# backplane.net
KiCad netlist of a schematic drawn in EAGLE
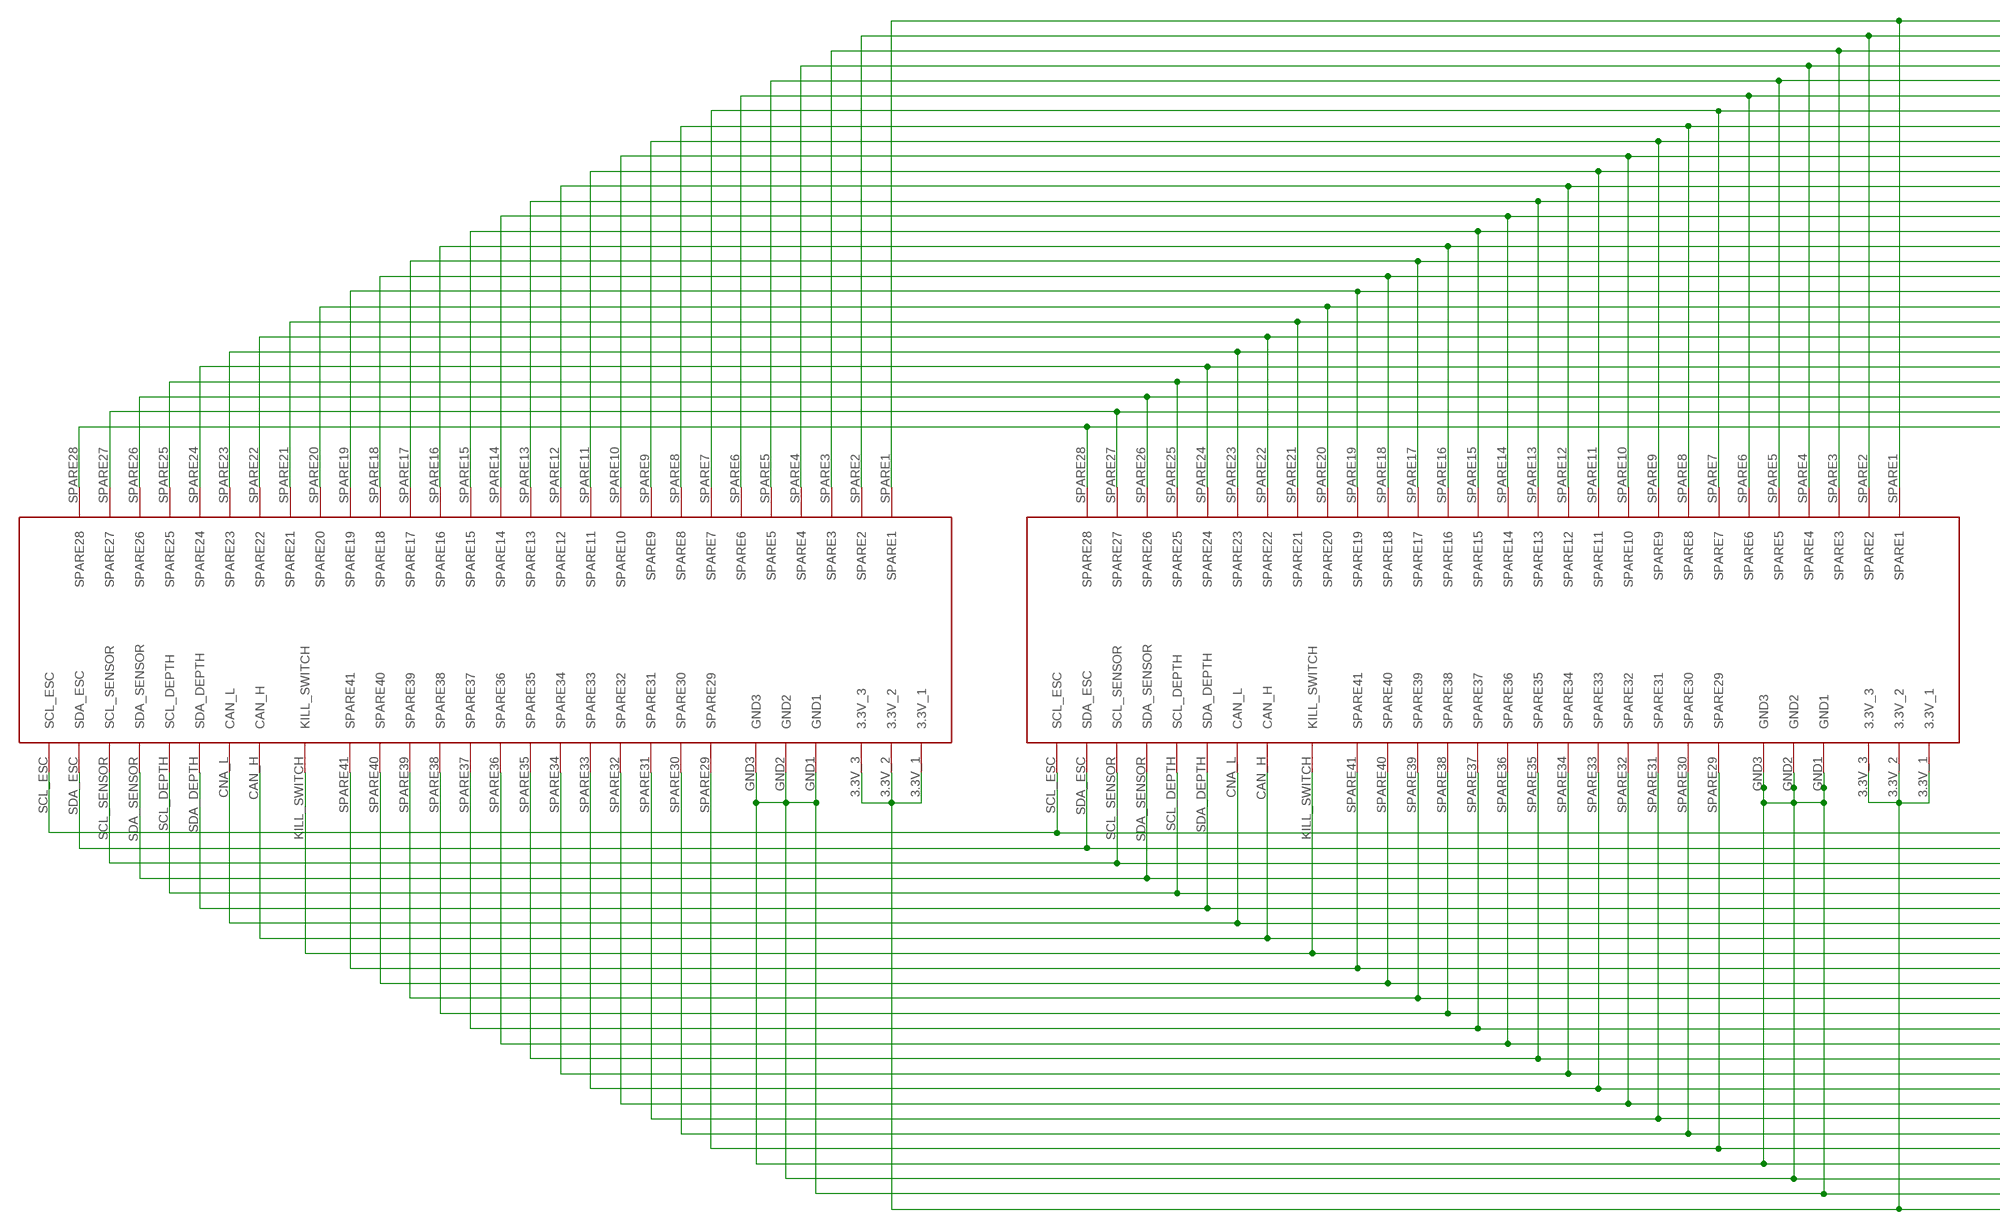
[diagram p0: schematic, sheet 1, part 1 of 2]
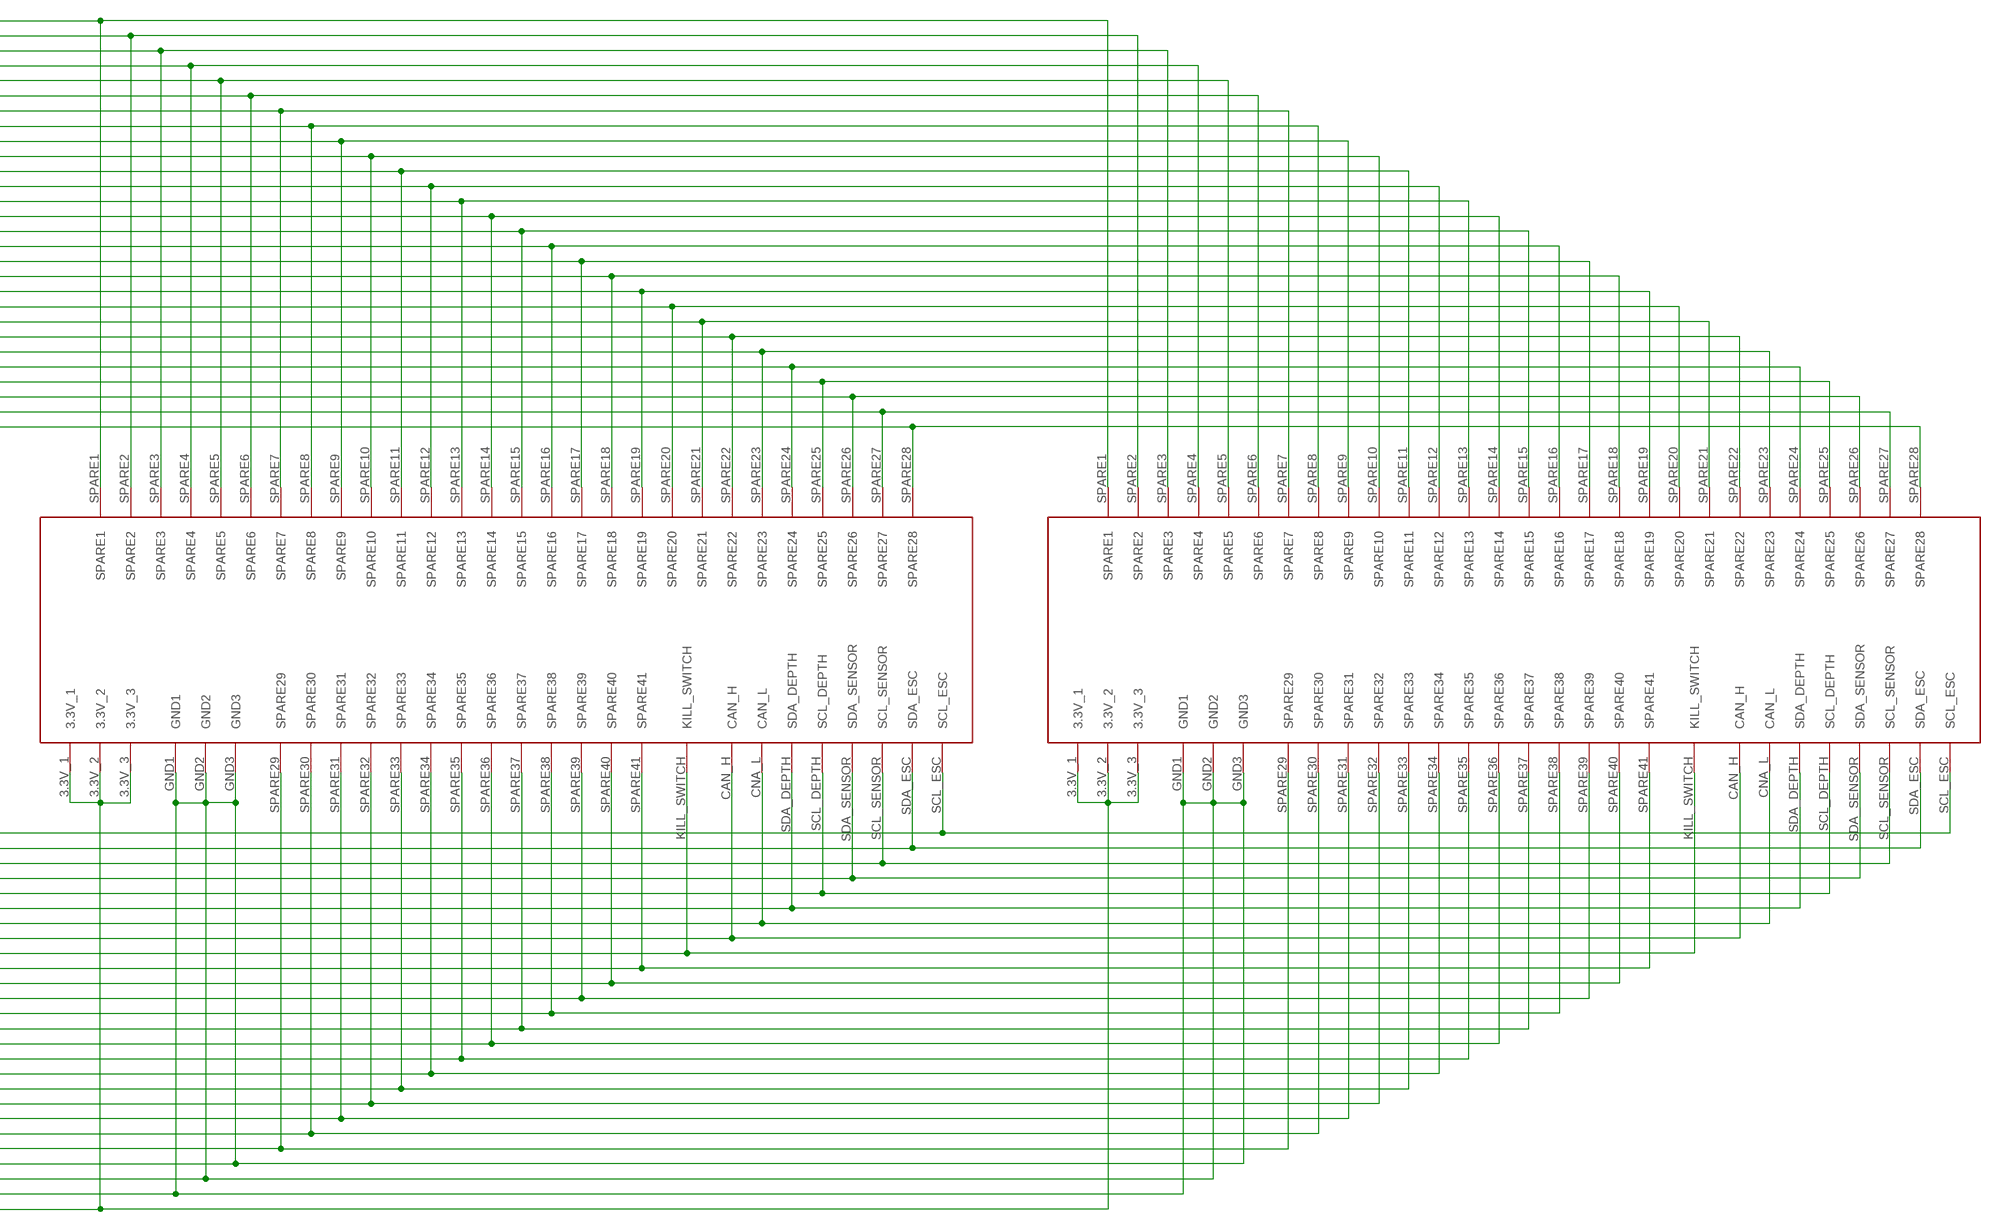
[diagram p1: schematic, sheet 1, part 2 of 2]

(export (version "E")
  (design (tool "Eeschema 10.0.6"))
  (components
    (comp (ref "CO-PROCESSOR")
      (value "5530843_MATE")
      (footprint "eagle-import:5530843-6-BACKPLANEMATE")
      (libsource (lib "eagle-import") (part "5530843_MATE"))
    )
    (comp (ref "CONVERTER")
      (value "5530843_MATE")
      (footprint "eagle-import:5530843-6-BACKPLANEMATE")
      (libsource (lib "eagle-import") (part "5530843_MATE"))
    )
    (comp (ref "EXTRA")
      (value "5530843_MATE")
      (footprint "eagle-import:5530843-6-BACKPLANEMATE")
      (libsource (lib "eagle-import") (part "5530843_MATE"))
    )
    (comp (ref "LOAD_BALANCER")
      (value "5530843_MATE")
      (footprint "eagle-import:5530843-6-BACKPLANEMATE")
      (libsource (lib "eagle-import") (part "5530843_MATE"))
    )
  )
  (nets
    (net (code "1") (name "/3.3") (class "Default")
      (node (ref "CO-PROCESSOR") (pin "3.3V_1") (pinfunction "3.3V_1_3.3V_1") (pintype "bidirectional"))
      (node (ref "CO-PROCESSOR") (pin "3.3V_2") (pinfunction "3.3V_2_3.3V_2") (pintype "bidirectional"))
      (node (ref "CO-PROCESSOR") (pin "3.3V_3") (pinfunction "3.3V_3_3.3V_3") (pintype "bidirectional"))
      (node (ref "CO-PROCESSOR") (pin "SPARE1") (pinfunction "SPARE1_SPARE1") (pintype "bidirectional"))
      (node (ref "CO-PROCESSOR") (pin "SPARE2") (pinfunction "SPARE2_SPARE2") (pintype "bidirectional"))
      (node (ref "CO-PROCESSOR") (pin "SPARE3") (pinfunction "SPARE3_SPARE3") (pintype "bidirectional"))
      (node (ref "CONVERTER") (pin "3.3V_1") (pinfunction "3.3V_1_3.3V_1") (pintype "bidirectional"))
      (node (ref "CONVERTER") (pin "3.3V_2") (pinfunction "3.3V_2_3.3V_2") (pintype "bidirectional"))
      (node (ref "CONVERTER") (pin "3.3V_3") (pinfunction "3.3V_3_3.3V_3") (pintype "bidirectional"))
      (node (ref "CONVERTER") (pin "SPARE1") (pinfunction "SPARE1_SPARE1") (pintype "bidirectional"))
      (node (ref "CONVERTER") (pin "SPARE2") (pinfunction "SPARE2_SPARE2") (pintype "bidirectional"))
      (node (ref "CONVERTER") (pin "SPARE3") (pinfunction "SPARE3_SPARE3") (pintype "bidirectional"))
      (node (ref "EXTRA") (pin "3.3V_1") (pinfunction "3.3V_1_3.3V_1") (pintype "bidirectional"))
      (node (ref "EXTRA") (pin "3.3V_2") (pinfunction "3.3V_2_3.3V_2") (pintype "bidirectional"))
      (node (ref "EXTRA") (pin "3.3V_3") (pinfunction "3.3V_3_3.3V_3") (pintype "bidirectional"))
      (node (ref "EXTRA") (pin "SPARE1") (pinfunction "SPARE1_SPARE1") (pintype "bidirectional"))
      (node (ref "EXTRA") (pin "SPARE2") (pinfunction "SPARE2_SPARE2") (pintype "bidirectional"))
      (node (ref "EXTRA") (pin "SPARE3") (pinfunction "SPARE3_SPARE3") (pintype "bidirectional"))
      (node (ref "LOAD_BALANCER") (pin "3.3V_1") (pinfunction "3.3V_1_3.3V_1") (pintype "bidirectional"))
      (node (ref "LOAD_BALANCER") (pin "3.3V_2") (pinfunction "3.3V_2_3.3V_2") (pintype "bidirectional"))
      (node (ref "LOAD_BALANCER") (pin "3.3V_3") (pinfunction "3.3V_3_3.3V_3") (pintype "bidirectional"))
      (node (ref "LOAD_BALANCER") (pin "SPARE1") (pinfunction "SPARE1_SPARE1") (pintype "bidirectional"))
      (node (ref "LOAD_BALANCER") (pin "SPARE2") (pinfunction "SPARE2_SPARE2") (pintype "bidirectional"))
      (node (ref "LOAD_BALANCER") (pin "SPARE3") (pinfunction "SPARE3_SPARE3") (pintype "bidirectional"))
    )
    (net (code "2") (name "/GND") (class "Default")
      (node (ref "CO-PROCESSOR") (pin "GND1") (pinfunction "GND1_GND1") (pintype "bidirectional"))
      (node (ref "CO-PROCESSOR") (pin "GND2") (pinfunction "GND2_GND2") (pintype "bidirectional"))
      (node (ref "CO-PROCESSOR") (pin "GND3") (pinfunction "GND3_GND3") (pintype "bidirectional"))
      (node (ref "CO-PROCESSOR") (pin "SPARE4") (pinfunction "SPARE4_SPARE4") (pintype "bidirectional"))
      (node (ref "CO-PROCESSOR") (pin "SPARE5") (pinfunction "SPARE5_SPARE5") (pintype "bidirectional"))
      (node (ref "CO-PROCESSOR") (pin "SPARE6") (pinfunction "SPARE6_SPARE6") (pintype "bidirectional"))
      (node (ref "CONVERTER") (pin "GND1") (pinfunction "GND1_GND1") (pintype "bidirectional"))
      (node (ref "CONVERTER") (pin "GND2") (pinfunction "GND2_GND2") (pintype "bidirectional"))
      (node (ref "CONVERTER") (pin "GND3") (pinfunction "GND3_GND3") (pintype "bidirectional"))
      (node (ref "CONVERTER") (pin "SPARE4") (pinfunction "SPARE4_SPARE4") (pintype "bidirectional"))
      (node (ref "CONVERTER") (pin "SPARE5") (pinfunction "SPARE5_SPARE5") (pintype "bidirectional"))
      (node (ref "CONVERTER") (pin "SPARE6") (pinfunction "SPARE6_SPARE6") (pintype "bidirectional"))
      (node (ref "EXTRA") (pin "GND1") (pinfunction "GND1_GND1") (pintype "bidirectional"))
      (node (ref "EXTRA") (pin "GND2") (pinfunction "GND2_GND2") (pintype "bidirectional"))
      (node (ref "EXTRA") (pin "GND3") (pinfunction "GND3_GND3") (pintype "bidirectional"))
      (node (ref "EXTRA") (pin "SPARE4") (pinfunction "SPARE4_SPARE4") (pintype "bidirectional"))
      (node (ref "EXTRA") (pin "SPARE5") (pinfunction "SPARE5_SPARE5") (pintype "bidirectional"))
      (node (ref "EXTRA") (pin "SPARE6") (pinfunction "SPARE6_SPARE6") (pintype "bidirectional"))
      (node (ref "LOAD_BALANCER") (pin "GND1") (pinfunction "GND1_GND1") (pintype "bidirectional"))
      (node (ref "LOAD_BALANCER") (pin "GND2") (pinfunction "GND2_GND2") (pintype "bidirectional"))
      (node (ref "LOAD_BALANCER") (pin "GND3") (pinfunction "GND3_GND3") (pintype "bidirectional"))
      (node (ref "LOAD_BALANCER") (pin "SPARE4") (pinfunction "SPARE4_SPARE4") (pintype "bidirectional"))
      (node (ref "LOAD_BALANCER") (pin "SPARE5") (pinfunction "SPARE5_SPARE5") (pintype "bidirectional"))
      (node (ref "LOAD_BALANCER") (pin "SPARE6") (pinfunction "SPARE6_SPARE6") (pintype "bidirectional"))
    )
    (net (code "3") (name "Net-(CO-PROCESSOR-CAN_L)") (class "Default")
      (node (ref "CO-PROCESSOR") (pin "CNA_L") (pinfunction "CAN_L_CNA_L") (pintype "bidirectional"))
      (node (ref "CONVERTER") (pin "CNA_L") (pinfunction "CAN_L_CNA_L") (pintype "bidirectional"))
      (node (ref "EXTRA") (pin "CNA_L") (pinfunction "CAN_L_CNA_L") (pintype "bidirectional"))
      (node (ref "LOAD_BALANCER") (pin "CNA_L") (pinfunction "CAN_L_CNA_L") (pintype "bidirectional"))
    )
    (net (code "4") (name "Net-(CO-PROCESSOR-PadCAN_H)") (class "Default")
      (node (ref "CO-PROCESSOR") (pin "CAN_H") (pinfunction "CAN_H_CAN_H") (pintype "bidirectional"))
      (node (ref "CONVERTER") (pin "CAN_H") (pinfunction "CAN_H_CAN_H") (pintype "bidirectional"))
      (node (ref "EXTRA") (pin "CAN_H") (pinfunction "CAN_H_CAN_H") (pintype "bidirectional"))
      (node (ref "LOAD_BALANCER") (pin "CAN_H") (pinfunction "CAN_H_CAN_H") (pintype "bidirectional"))
    )
    (net (code "5") (name "Net-(CO-PROCESSOR-PadKILL_SWITCH)") (class "Default")
      (node (ref "CO-PROCESSOR") (pin "KILL_SWITCH") (pinfunction "KILL_SWITCH_KILL_SWITCH") (pintype "bidirectional"))
      (node (ref "CONVERTER") (pin "KILL_SWITCH") (pinfunction "KILL_SWITCH_KILL_SWITCH") (pintype "bidirectional"))
      (node (ref "EXTRA") (pin "KILL_SWITCH") (pinfunction "KILL_SWITCH_KILL_SWITCH") (pintype "bidirectional"))
      (node (ref "LOAD_BALANCER") (pin "KILL_SWITCH") (pinfunction "KILL_SWITCH_KILL_SWITCH") (pintype "bidirectional"))
    )
    (net (code "6") (name "Net-(CO-PROCESSOR-PadSCL_DEPTH)") (class "Default")
      (node (ref "CO-PROCESSOR") (pin "SCL_DEPTH") (pinfunction "SCL_DEPTH_SCL_DEPTH") (pintype "bidirectional"))
      (node (ref "CONVERTER") (pin "SCL_DEPTH") (pinfunction "SCL_DEPTH_SCL_DEPTH") (pintype "bidirectional"))
      (node (ref "EXTRA") (pin "SCL_DEPTH") (pinfunction "SCL_DEPTH_SCL_DEPTH") (pintype "bidirectional"))
      (node (ref "LOAD_BALANCER") (pin "SCL_DEPTH") (pinfunction "SCL_DEPTH_SCL_DEPTH") (pintype "bidirectional"))
    )
    (net (code "7") (name "Net-(CO-PROCESSOR-PadSCL_ESC)") (class "Default")
      (node (ref "CO-PROCESSOR") (pin "SCL_ESC") (pinfunction "SCL_ESC_SCL_ESC") (pintype "bidirectional"))
      (node (ref "CONVERTER") (pin "SCL_ESC") (pinfunction "SCL_ESC_SCL_ESC") (pintype "bidirectional"))
      (node (ref "EXTRA") (pin "SCL_ESC") (pinfunction "SCL_ESC_SCL_ESC") (pintype "bidirectional"))
      (node (ref "LOAD_BALANCER") (pin "SCL_ESC") (pinfunction "SCL_ESC_SCL_ESC") (pintype "bidirectional"))
    )
    (net (code "8") (name "Net-(CO-PROCESSOR-PadSCL_SENSOR)") (class "Default")
      (node (ref "CO-PROCESSOR") (pin "SCL_SENSOR") (pinfunction "SCL_SENSOR_SCL_SENSOR") (pintype "bidirectional"))
      (node (ref "CONVERTER") (pin "SCL_SENSOR") (pinfunction "SCL_SENSOR_SCL_SENSOR") (pintype "bidirectional"))
      (node (ref "EXTRA") (pin "SCL_SENSOR") (pinfunction "SCL_SENSOR_SCL_SENSOR") (pintype "bidirectional"))
      (node (ref "LOAD_BALANCER") (pin "SCL_SENSOR") (pinfunction "SCL_SENSOR_SCL_SENSOR") (pintype "bidirectional"))
    )
    (net (code "9") (name "Net-(CO-PROCESSOR-PadSDA_DEPTH)") (class "Default")
      (node (ref "CO-PROCESSOR") (pin "SDA_DEPTH") (pinfunction "SDA_DEPTH_SDA_DEPTH") (pintype "bidirectional"))
      (node (ref "CONVERTER") (pin "SDA_DEPTH") (pinfunction "SDA_DEPTH_SDA_DEPTH") (pintype "bidirectional"))
      (node (ref "EXTRA") (pin "SDA_DEPTH") (pinfunction "SDA_DEPTH_SDA_DEPTH") (pintype "bidirectional"))
      (node (ref "LOAD_BALANCER") (pin "SDA_DEPTH") (pinfunction "SDA_DEPTH_SDA_DEPTH") (pintype "bidirectional"))
    )
    (net (code "10") (name "Net-(CO-PROCESSOR-PadSDA_ESC)") (class "Default")
      (node (ref "CO-PROCESSOR") (pin "SDA_ESC") (pinfunction "SDA_ESC_SDA_ESC") (pintype "bidirectional"))
      (node (ref "CONVERTER") (pin "SDA_ESC") (pinfunction "SDA_ESC_SDA_ESC") (pintype "bidirectional"))
      (node (ref "EXTRA") (pin "SDA_ESC") (pinfunction "SDA_ESC_SDA_ESC") (pintype "bidirectional"))
      (node (ref "LOAD_BALANCER") (pin "SDA_ESC") (pinfunction "SDA_ESC_SDA_ESC") (pintype "bidirectional"))
    )
    (net (code "11") (name "Net-(CO-PROCESSOR-PadSDA_SENSOR)") (class "Default")
      (node (ref "CO-PROCESSOR") (pin "SDA_SENSOR") (pinfunction "SDA_SENSOR_SDA_SENSOR") (pintype "bidirectional"))
      (node (ref "CONVERTER") (pin "SDA_SENSOR") (pinfunction "SDA_SENSOR_SDA_SENSOR") (pintype "bidirectional"))
      (node (ref "EXTRA") (pin "SDA_SENSOR") (pinfunction "SDA_SENSOR_SDA_SENSOR") (pintype "bidirectional"))
      (node (ref "LOAD_BALANCER") (pin "SDA_SENSOR") (pinfunction "SDA_SENSOR_SDA_SENSOR") (pintype "bidirectional"))
    )
    (net (code "12") (name "Net-(CO-PROCESSOR-PadSPARE7)") (class "Default")
      (node (ref "CO-PROCESSOR") (pin "SPARE7") (pinfunction "SPARE7_SPARE7") (pintype "bidirectional"))
      (node (ref "CONVERTER") (pin "SPARE7") (pinfunction "SPARE7_SPARE7") (pintype "bidirectional"))
      (node (ref "EXTRA") (pin "SPARE7") (pinfunction "SPARE7_SPARE7") (pintype "bidirectional"))
      (node (ref "LOAD_BALANCER") (pin "SPARE7") (pinfunction "SPARE7_SPARE7") (pintype "bidirectional"))
    )
    (net (code "13") (name "Net-(CO-PROCESSOR-PadSPARE8)") (class "Default")
      (node (ref "CO-PROCESSOR") (pin "SPARE8") (pinfunction "SPARE8_SPARE8") (pintype "bidirectional"))
      (node (ref "CONVERTER") (pin "SPARE8") (pinfunction "SPARE8_SPARE8") (pintype "bidirectional"))
      (node (ref "EXTRA") (pin "SPARE8") (pinfunction "SPARE8_SPARE8") (pintype "bidirectional"))
      (node (ref "LOAD_BALANCER") (pin "SPARE8") (pinfunction "SPARE8_SPARE8") (pintype "bidirectional"))
    )
    (net (code "14") (name "Net-(CO-PROCESSOR-PadSPARE9)") (class "Default")
      (node (ref "CO-PROCESSOR") (pin "SPARE9") (pinfunction "SPARE9_SPARE9") (pintype "bidirectional"))
      (node (ref "CONVERTER") (pin "SPARE9") (pinfunction "SPARE9_SPARE9") (pintype "bidirectional"))
      (node (ref "EXTRA") (pin "SPARE9") (pinfunction "SPARE9_SPARE9") (pintype "bidirectional"))
      (node (ref "LOAD_BALANCER") (pin "SPARE9") (pinfunction "SPARE9_SPARE9") (pintype "bidirectional"))
    )
    (net (code "15") (name "Net-(CO-PROCESSOR-PadSPARE10)") (class "Default")
      (node (ref "CO-PROCESSOR") (pin "SPARE10") (pinfunction "SPARE10_SPARE10") (pintype "bidirectional"))
      (node (ref "CONVERTER") (pin "SPARE10") (pinfunction "SPARE10_SPARE10") (pintype "bidirectional"))
      (node (ref "EXTRA") (pin "SPARE10") (pinfunction "SPARE10_SPARE10") (pintype "bidirectional"))
      (node (ref "LOAD_BALANCER") (pin "SPARE10") (pinfunction "SPARE10_SPARE10") (pintype "bidirectional"))
    )
    (net (code "16") (name "Net-(CO-PROCESSOR-PadSPARE11)") (class "Default")
      (node (ref "CO-PROCESSOR") (pin "SPARE11") (pinfunction "SPARE11_SPARE11") (pintype "bidirectional"))
      (node (ref "CONVERTER") (pin "SPARE11") (pinfunction "SPARE11_SPARE11") (pintype "bidirectional"))
      (node (ref "EXTRA") (pin "SPARE11") (pinfunction "SPARE11_SPARE11") (pintype "bidirectional"))
      (node (ref "LOAD_BALANCER") (pin "SPARE11") (pinfunction "SPARE11_SPARE11") (pintype "bidirectional"))
    )
    (net (code "17") (name "Net-(CO-PROCESSOR-PadSPARE12)") (class "Default")
      (node (ref "CO-PROCESSOR") (pin "SPARE12") (pinfunction "SPARE12_SPARE12") (pintype "bidirectional"))
      (node (ref "CONVERTER") (pin "SPARE12") (pinfunction "SPARE12_SPARE12") (pintype "bidirectional"))
      (node (ref "EXTRA") (pin "SPARE12") (pinfunction "SPARE12_SPARE12") (pintype "bidirectional"))
      (node (ref "LOAD_BALANCER") (pin "SPARE12") (pinfunction "SPARE12_SPARE12") (pintype "bidirectional"))
    )
    (net (code "18") (name "Net-(CO-PROCESSOR-PadSPARE13)") (class "Default")
      (node (ref "CO-PROCESSOR") (pin "SPARE13") (pinfunction "SPARE13_SPARE13") (pintype "bidirectional"))
      (node (ref "CONVERTER") (pin "SPARE13") (pinfunction "SPARE13_SPARE13") (pintype "bidirectional"))
      (node (ref "EXTRA") (pin "SPARE13") (pinfunction "SPARE13_SPARE13") (pintype "bidirectional"))
      (node (ref "LOAD_BALANCER") (pin "SPARE13") (pinfunction "SPARE13_SPARE13") (pintype "bidirectional"))
    )
    (net (code "19") (name "Net-(CO-PROCESSOR-PadSPARE14)") (class "Default")
      (node (ref "CO-PROCESSOR") (pin "SPARE14") (pinfunction "SPARE14_SPARE14") (pintype "bidirectional"))
      (node (ref "CONVERTER") (pin "SPARE14") (pinfunction "SPARE14_SPARE14") (pintype "bidirectional"))
      (node (ref "EXTRA") (pin "SPARE14") (pinfunction "SPARE14_SPARE14") (pintype "bidirectional"))
      (node (ref "LOAD_BALANCER") (pin "SPARE14") (pinfunction "SPARE14_SPARE14") (pintype "bidirectional"))
    )
    (net (code "20") (name "Net-(CO-PROCESSOR-PadSPARE15)") (class "Default")
      (node (ref "CO-PROCESSOR") (pin "SPARE15") (pinfunction "SPARE15_SPARE15") (pintype "bidirectional"))
      (node (ref "CONVERTER") (pin "SPARE15") (pinfunction "SPARE15_SPARE15") (pintype "bidirectional"))
      (node (ref "EXTRA") (pin "SPARE15") (pinfunction "SPARE15_SPARE15") (pintype "bidirectional"))
      (node (ref "LOAD_BALANCER") (pin "SPARE15") (pinfunction "SPARE15_SPARE15") (pintype "bidirectional"))
    )
    (net (code "21") (name "Net-(CO-PROCESSOR-PadSPARE16)") (class "Default")
      (node (ref "CO-PROCESSOR") (pin "SPARE16") (pinfunction "SPARE16_SPARE16") (pintype "bidirectional"))
      (node (ref "CONVERTER") (pin "SPARE16") (pinfunction "SPARE16_SPARE16") (pintype "bidirectional"))
      (node (ref "EXTRA") (pin "SPARE16") (pinfunction "SPARE16_SPARE16") (pintype "bidirectional"))
      (node (ref "LOAD_BALANCER") (pin "SPARE16") (pinfunction "SPARE16_SPARE16") (pintype "bidirectional"))
    )
    (net (code "22") (name "Net-(CO-PROCESSOR-PadSPARE17)") (class "Default")
      (node (ref "CO-PROCESSOR") (pin "SPARE17") (pinfunction "SPARE17_SPARE17") (pintype "bidirectional"))
      (node (ref "CONVERTER") (pin "SPARE17") (pinfunction "SPARE17_SPARE17") (pintype "bidirectional"))
      (node (ref "EXTRA") (pin "SPARE17") (pinfunction "SPARE17_SPARE17") (pintype "bidirectional"))
      (node (ref "LOAD_BALANCER") (pin "SPARE17") (pinfunction "SPARE17_SPARE17") (pintype "bidirectional"))
    )
    (net (code "23") (name "Net-(CO-PROCESSOR-PadSPARE18)") (class "Default")
      (node (ref "CO-PROCESSOR") (pin "SPARE18") (pinfunction "SPARE18_SPARE18") (pintype "bidirectional"))
      (node (ref "CONVERTER") (pin "SPARE18") (pinfunction "SPARE18_SPARE18") (pintype "bidirectional"))
      (node (ref "EXTRA") (pin "SPARE18") (pinfunction "SPARE18_SPARE18") (pintype "bidirectional"))
      (node (ref "LOAD_BALANCER") (pin "SPARE18") (pinfunction "SPARE18_SPARE18") (pintype "bidirectional"))
    )
    (net (code "24") (name "Net-(CO-PROCESSOR-PadSPARE19)") (class "Default")
      (node (ref "CO-PROCESSOR") (pin "SPARE19") (pinfunction "SPARE19_SPARE19") (pintype "bidirectional"))
      (node (ref "CONVERTER") (pin "SPARE19") (pinfunction "SPARE19_SPARE19") (pintype "bidirectional"))
      (node (ref "EXTRA") (pin "SPARE19") (pinfunction "SPARE19_SPARE19") (pintype "bidirectional"))
      (node (ref "LOAD_BALANCER") (pin "SPARE19") (pinfunction "SPARE19_SPARE19") (pintype "bidirectional"))
    )
    (net (code "25") (name "Net-(CO-PROCESSOR-PadSPARE20)") (class "Default")
      (node (ref "CO-PROCESSOR") (pin "SPARE20") (pinfunction "SPARE20_SPARE20") (pintype "bidirectional"))
      (node (ref "CONVERTER") (pin "SPARE20") (pinfunction "SPARE20_SPARE20") (pintype "bidirectional"))
      (node (ref "EXTRA") (pin "SPARE20") (pinfunction "SPARE20_SPARE20") (pintype "bidirectional"))
      (node (ref "LOAD_BALANCER") (pin "SPARE20") (pinfunction "SPARE20_SPARE20") (pintype "bidirectional"))
    )
    (net (code "26") (name "Net-(CO-PROCESSOR-PadSPARE21)") (class "Default")
      (node (ref "CO-PROCESSOR") (pin "SPARE21") (pinfunction "SPARE21_SPARE21") (pintype "bidirectional"))
      (node (ref "CONVERTER") (pin "SPARE21") (pinfunction "SPARE21_SPARE21") (pintype "bidirectional"))
      (node (ref "EXTRA") (pin "SPARE21") (pinfunction "SPARE21_SPARE21") (pintype "bidirectional"))
      (node (ref "LOAD_BALANCER") (pin "SPARE21") (pinfunction "SPARE21_SPARE21") (pintype "bidirectional"))
    )
    (net (code "27") (name "Net-(CO-PROCESSOR-PadSPARE22)") (class "Default")
      (node (ref "CO-PROCESSOR") (pin "SPARE22") (pinfunction "SPARE22_SPARE22") (pintype "bidirectional"))
      (node (ref "CONVERTER") (pin "SPARE22") (pinfunction "SPARE22_SPARE22") (pintype "bidirectional"))
      (node (ref "EXTRA") (pin "SPARE22") (pinfunction "SPARE22_SPARE22") (pintype "bidirectional"))
      (node (ref "LOAD_BALANCER") (pin "SPARE22") (pinfunction "SPARE22_SPARE22") (pintype "bidirectional"))
    )
    (net (code "28") (name "Net-(CO-PROCESSOR-PadSPARE23)") (class "Default")
      (node (ref "CO-PROCESSOR") (pin "SPARE23") (pinfunction "SPARE23_SPARE23") (pintype "bidirectional"))
      (node (ref "CONVERTER") (pin "SPARE23") (pinfunction "SPARE23_SPARE23") (pintype "bidirectional"))
      (node (ref "EXTRA") (pin "SPARE23") (pinfunction "SPARE23_SPARE23") (pintype "bidirectional"))
      (node (ref "LOAD_BALANCER") (pin "SPARE23") (pinfunction "SPARE23_SPARE23") (pintype "bidirectional"))
    )
    (net (code "29") (name "Net-(CO-PROCESSOR-PadSPARE24)") (class "Default")
      (node (ref "CO-PROCESSOR") (pin "SPARE24") (pinfunction "SPARE24_SPARE24") (pintype "bidirectional"))
      (node (ref "CONVERTER") (pin "SPARE24") (pinfunction "SPARE24_SPARE24") (pintype "bidirectional"))
      (node (ref "EXTRA") (pin "SPARE24") (pinfunction "SPARE24_SPARE24") (pintype "bidirectional"))
      (node (ref "LOAD_BALANCER") (pin "SPARE24") (pinfunction "SPARE24_SPARE24") (pintype "bidirectional"))
    )
    (net (code "30") (name "Net-(CO-PROCESSOR-PadSPARE25)") (class "Default")
      (node (ref "CO-PROCESSOR") (pin "SPARE25") (pinfunction "SPARE25_SPARE25") (pintype "bidirectional"))
      (node (ref "CONVERTER") (pin "SPARE25") (pinfunction "SPARE25_SPARE25") (pintype "bidirectional"))
      (node (ref "EXTRA") (pin "SPARE25") (pinfunction "SPARE25_SPARE25") (pintype "bidirectional"))
      (node (ref "LOAD_BALANCER") (pin "SPARE25") (pinfunction "SPARE25_SPARE25") (pintype "bidirectional"))
    )
    (net (code "31") (name "Net-(CO-PROCESSOR-PadSPARE26)") (class "Default")
      (node (ref "CO-PROCESSOR") (pin "SPARE26") (pinfunction "SPARE26_SPARE26") (pintype "bidirectional"))
      (node (ref "CONVERTER") (pin "SPARE26") (pinfunction "SPARE26_SPARE26") (pintype "bidirectional"))
      (node (ref "EXTRA") (pin "SPARE26") (pinfunction "SPARE26_SPARE26") (pintype "bidirectional"))
      (node (ref "LOAD_BALANCER") (pin "SPARE26") (pinfunction "SPARE26_SPARE26") (pintype "bidirectional"))
    )
    (net (code "32") (name "Net-(CO-PROCESSOR-PadSPARE27)") (class "Default")
      (node (ref "CO-PROCESSOR") (pin "SPARE27") (pinfunction "SPARE27_SPARE27") (pintype "bidirectional"))
      (node (ref "CONVERTER") (pin "SPARE27") (pinfunction "SPARE27_SPARE27") (pintype "bidirectional"))
      (node (ref "EXTRA") (pin "SPARE27") (pinfunction "SPARE27_SPARE27") (pintype "bidirectional"))
      (node (ref "LOAD_BALANCER") (pin "SPARE27") (pinfunction "SPARE27_SPARE27") (pintype "bidirectional"))
    )
    (net (code "33") (name "Net-(CO-PROCESSOR-PadSPARE28)") (class "Default")
      (node (ref "CO-PROCESSOR") (pin "SPARE28") (pinfunction "SPARE28_SPARE28") (pintype "bidirectional"))
      (node (ref "CONVERTER") (pin "SPARE28") (pinfunction "SPARE28_SPARE28") (pintype "bidirectional"))
      (node (ref "EXTRA") (pin "SPARE28") (pinfunction "SPARE28_SPARE28") (pintype "bidirectional"))
      (node (ref "LOAD_BALANCER") (pin "SPARE28") (pinfunction "SPARE28_SPARE28") (pintype "bidirectional"))
    )
    (net (code "34") (name "Net-(CO-PROCESSOR-PadSPARE29)") (class "Default")
      (node (ref "CO-PROCESSOR") (pin "SPARE29") (pinfunction "SPARE29_SPARE29") (pintype "bidirectional"))
      (node (ref "CONVERTER") (pin "SPARE29") (pinfunction "SPARE29_SPARE29") (pintype "bidirectional"))
      (node (ref "EXTRA") (pin "SPARE29") (pinfunction "SPARE29_SPARE29") (pintype "bidirectional"))
      (node (ref "LOAD_BALANCER") (pin "SPARE29") (pinfunction "SPARE29_SPARE29") (pintype "bidirectional"))
    )
    (net (code "35") (name "Net-(CO-PROCESSOR-PadSPARE30)") (class "Default")
      (node (ref "CO-PROCESSOR") (pin "SPARE30") (pinfunction "SPARE30_SPARE30") (pintype "bidirectional"))
      (node (ref "CONVERTER") (pin "SPARE30") (pinfunction "SPARE30_SPARE30") (pintype "bidirectional"))
      (node (ref "EXTRA") (pin "SPARE30") (pinfunction "SPARE30_SPARE30") (pintype "bidirectional"))
      (node (ref "LOAD_BALANCER") (pin "SPARE30") (pinfunction "SPARE30_SPARE30") (pintype "bidirectional"))
    )
    (net (code "36") (name "Net-(CO-PROCESSOR-PadSPARE31)") (class "Default")
      (node (ref "CO-PROCESSOR") (pin "SPARE31") (pinfunction "SPARE31_SPARE31") (pintype "bidirectional"))
      (node (ref "CONVERTER") (pin "SPARE31") (pinfunction "SPARE31_SPARE31") (pintype "bidirectional"))
      (node (ref "EXTRA") (pin "SPARE31") (pinfunction "SPARE31_SPARE31") (pintype "bidirectional"))
      (node (ref "LOAD_BALANCER") (pin "SPARE31") (pinfunction "SPARE31_SPARE31") (pintype "bidirectional"))
    )
    (net (code "37") (name "Net-(CO-PROCESSOR-PadSPARE32)") (class "Default")
      (node (ref "CO-PROCESSOR") (pin "SPARE32") (pinfunction "SPARE32_SPARE32") (pintype "bidirectional"))
      (node (ref "CONVERTER") (pin "SPARE32") (pinfunction "SPARE32_SPARE32") (pintype "bidirectional"))
      (node (ref "EXTRA") (pin "SPARE32") (pinfunction "SPARE32_SPARE32") (pintype "bidirectional"))
      (node (ref "LOAD_BALANCER") (pin "SPARE32") (pinfunction "SPARE32_SPARE32") (pintype "bidirectional"))
    )
    (net (code "38") (name "Net-(CO-PROCESSOR-PadSPARE33)") (class "Default")
      (node (ref "CO-PROCESSOR") (pin "SPARE33") (pinfunction "SPARE33_SPARE33") (pintype "bidirectional"))
      (node (ref "CONVERTER") (pin "SPARE33") (pinfunction "SPARE33_SPARE33") (pintype "bidirectional"))
      (node (ref "EXTRA") (pin "SPARE33") (pinfunction "SPARE33_SPARE33") (pintype "bidirectional"))
      (node (ref "LOAD_BALANCER") (pin "SPARE33") (pinfunction "SPARE33_SPARE33") (pintype "bidirectional"))
    )
    (net (code "39") (name "Net-(CO-PROCESSOR-PadSPARE34)") (class "Default")
      (node (ref "CO-PROCESSOR") (pin "SPARE34") (pinfunction "SPARE34_SPARE34") (pintype "bidirectional"))
      (node (ref "CONVERTER") (pin "SPARE34") (pinfunction "SPARE34_SPARE34") (pintype "bidirectional"))
      (node (ref "EXTRA") (pin "SPARE34") (pinfunction "SPARE34_SPARE34") (pintype "bidirectional"))
      (node (ref "LOAD_BALANCER") (pin "SPARE34") (pinfunction "SPARE34_SPARE34") (pintype "bidirectional"))
    )
    (net (code "40") (name "Net-(CO-PROCESSOR-PadSPARE35)") (class "Default")
      (node (ref "CO-PROCESSOR") (pin "SPARE35") (pinfunction "SPARE35_SPARE35") (pintype "bidirectional"))
      (node (ref "CONVERTER") (pin "SPARE35") (pinfunction "SPARE35_SPARE35") (pintype "bidirectional"))
      (node (ref "EXTRA") (pin "SPARE35") (pinfunction "SPARE35_SPARE35") (pintype "bidirectional"))
      (node (ref "LOAD_BALANCER") (pin "SPARE35") (pinfunction "SPARE35_SPARE35") (pintype "bidirectional"))
    )
    (net (code "41") (name "Net-(CO-PROCESSOR-PadSPARE36)") (class "Default")
      (node (ref "CO-PROCESSOR") (pin "SPARE36") (pinfunction "SPARE36_SPARE36") (pintype "bidirectional"))
      (node (ref "CONVERTER") (pin "SPARE36") (pinfunction "SPARE36_SPARE36") (pintype "bidirectional"))
      (node (ref "EXTRA") (pin "SPARE36") (pinfunction "SPARE36_SPARE36") (pintype "bidirectional"))
      (node (ref "LOAD_BALANCER") (pin "SPARE36") (pinfunction "SPARE36_SPARE36") (pintype "bidirectional"))
    )
    (net (code "42") (name "Net-(CO-PROCESSOR-PadSPARE37)") (class "Default")
      (node (ref "CO-PROCESSOR") (pin "SPARE37") (pinfunction "SPARE37_SPARE37") (pintype "bidirectional"))
      (node (ref "CONVERTER") (pin "SPARE37") (pinfunction "SPARE37_SPARE37") (pintype "bidirectional"))
      (node (ref "EXTRA") (pin "SPARE37") (pinfunction "SPARE37_SPARE37") (pintype "bidirectional"))
      (node (ref "LOAD_BALANCER") (pin "SPARE37") (pinfunction "SPARE37_SPARE37") (pintype "bidirectional"))
    )
    (net (code "43") (name "Net-(CO-PROCESSOR-PadSPARE38)") (class "Default")
      (node (ref "CO-PROCESSOR") (pin "SPARE38") (pinfunction "SPARE38_SPARE38") (pintype "bidirectional"))
      (node (ref "CONVERTER") (pin "SPARE38") (pinfunction "SPARE38_SPARE38") (pintype "bidirectional"))
      (node (ref "EXTRA") (pin "SPARE38") (pinfunction "SPARE38_SPARE38") (pintype "bidirectional"))
      (node (ref "LOAD_BALANCER") (pin "SPARE38") (pinfunction "SPARE38_SPARE38") (pintype "bidirectional"))
    )
    (net (code "44") (name "Net-(CO-PROCESSOR-PadSPARE39)") (class "Default")
      (node (ref "CO-PROCESSOR") (pin "SPARE39") (pinfunction "SPARE39_SPARE39") (pintype "bidirectional"))
      (node (ref "CONVERTER") (pin "SPARE39") (pinfunction "SPARE39_SPARE39") (pintype "bidirectional"))
      (node (ref "EXTRA") (pin "SPARE39") (pinfunction "SPARE39_SPARE39") (pintype "bidirectional"))
      (node (ref "LOAD_BALANCER") (pin "SPARE39") (pinfunction "SPARE39_SPARE39") (pintype "bidirectional"))
    )
    (net (code "45") (name "Net-(CO-PROCESSOR-PadSPARE40)") (class "Default")
      (node (ref "CO-PROCESSOR") (pin "SPARE40") (pinfunction "SPARE40_SPARE40") (pintype "bidirectional"))
      (node (ref "CONVERTER") (pin "SPARE40") (pinfunction "SPARE40_SPARE40") (pintype "bidirectional"))
      (node (ref "EXTRA") (pin "SPARE40") (pinfunction "SPARE40_SPARE40") (pintype "bidirectional"))
      (node (ref "LOAD_BALANCER") (pin "SPARE40") (pinfunction "SPARE40_SPARE40") (pintype "bidirectional"))
    )
    (net (code "46") (name "Net-(CO-PROCESSOR-PadSPARE41)") (class "Default")
      (node (ref "CO-PROCESSOR") (pin "SPARE41") (pinfunction "SPARE41_SPARE41") (pintype "bidirectional"))
      (node (ref "CONVERTER") (pin "SPARE41") (pinfunction "SPARE41_SPARE41") (pintype "bidirectional"))
      (node (ref "EXTRA") (pin "SPARE41") (pinfunction "SPARE41_SPARE41") (pintype "bidirectional"))
      (node (ref "LOAD_BALANCER") (pin "SPARE41") (pinfunction "SPARE41_SPARE41") (pintype "bidirectional"))
    )
  )
)
